# clock_driver_board.net
KiCad netlist of a schematic drawn in EAGLE
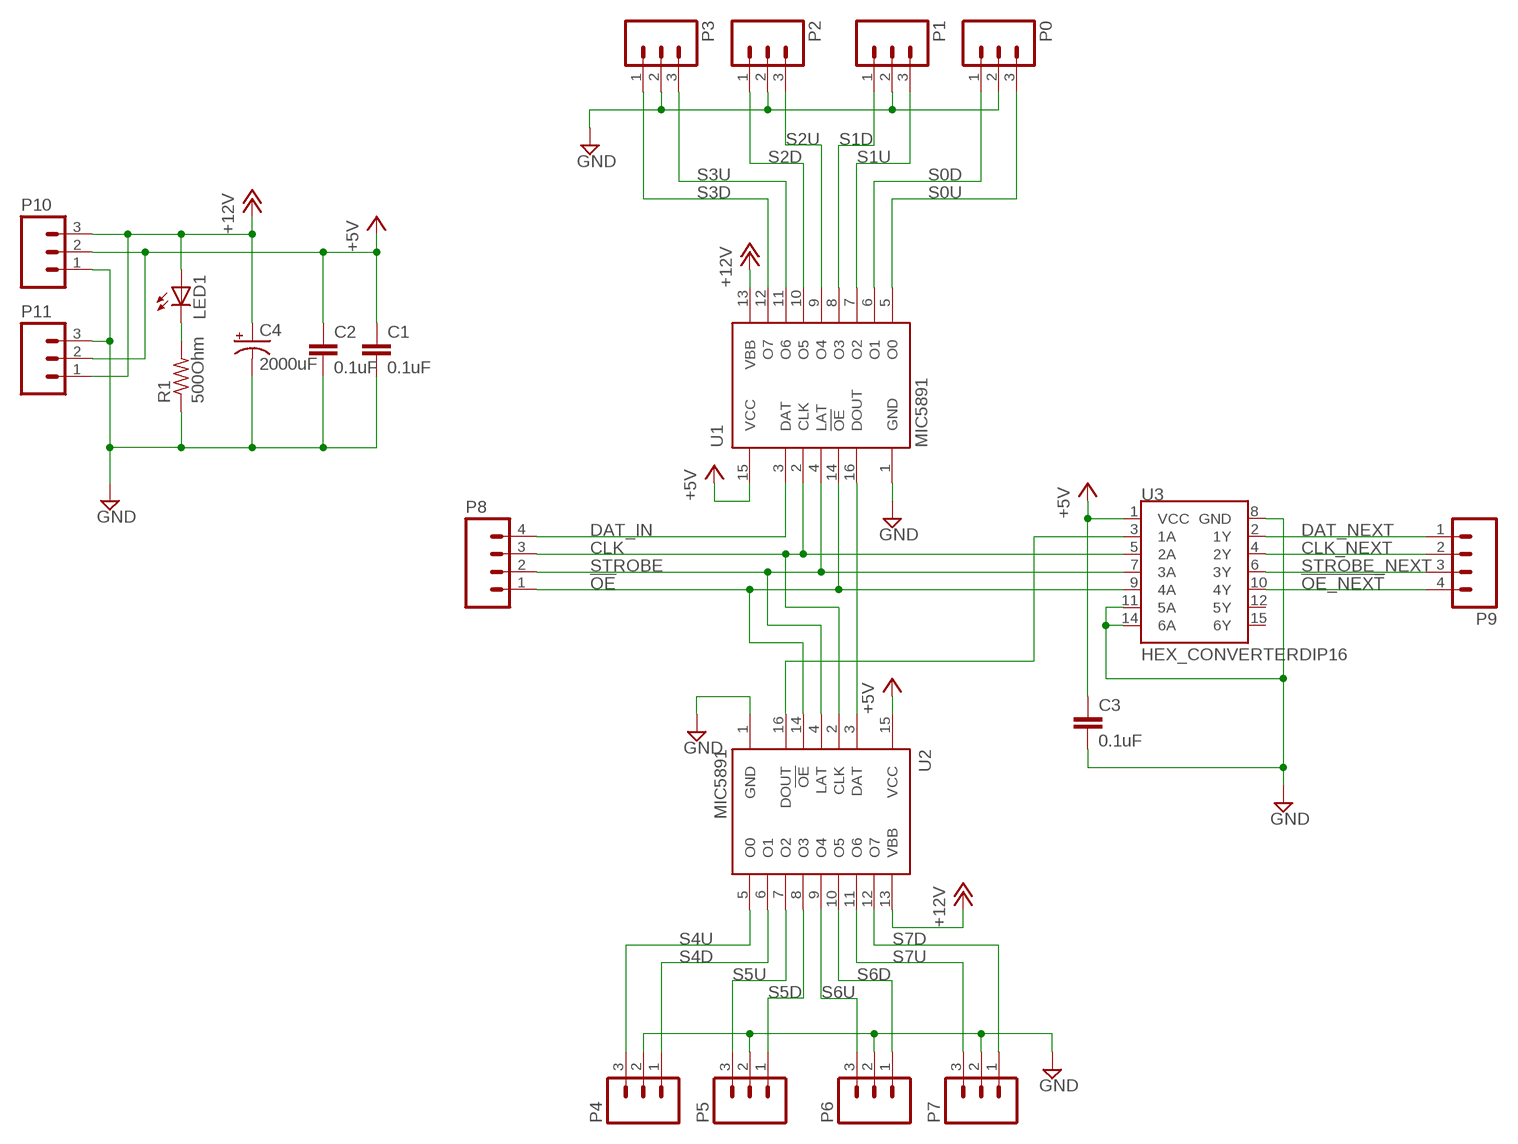
[diagram p0: schematic, sheet 1]

(export (version "E")
  (design (tool "Eeschema 10.0.6"))
  (components
    (comp (ref "C1")
      (value "0.1uF")
      (footprint "eagle-import:C2.5-2")
      (libsource (lib "eagle-import") (part "C2.5/2"))
    )
    (comp (ref "C2")
      (value "0.1uF")
      (footprint "eagle-import:C2.5-2")
      (libsource (lib "eagle-import") (part "C2.5/2"))
    )
    (comp (ref "C3")
      (value "0.1uF")
      (footprint "eagle-import:C2.5-2")
      (libsource (lib "eagle-import") (part "C2.5/2"))
    )
    (comp (ref "C4")
      (value "2000uF")
      (footprint "eagle-import:E7,5-16")
      (libsource (lib "eagle-import") (part "CPOL-USE7.5-16"))
    )
    (comp (ref "LED1")
      (value "LED3MM")
      (footprint "eagle-import:LED3MM")
      (libsource (lib "eagle-import") (part "LED3MM"))
    )
    (comp (ref "P0")
      (value "M03LONGPADS")
      (footprint "eagle-import:1X03_LONGPADS")
      (libsource (lib "eagle-import") (part "M03LONGPADS"))
    )
    (comp (ref "P1")
      (value "M03LONGPADS")
      (footprint "eagle-import:1X03_LONGPADS")
      (libsource (lib "eagle-import") (part "M03LONGPADS"))
    )
    (comp (ref "P2")
      (value "M03LONGPADS")
      (footprint "eagle-import:1X03_LONGPADS")
      (libsource (lib "eagle-import") (part "M03LONGPADS"))
    )
    (comp (ref "P3")
      (value "M03LONGPADS")
      (footprint "eagle-import:1X03_LONGPADS")
      (libsource (lib "eagle-import") (part "M03LONGPADS"))
    )
    (comp (ref "P4")
      (value "M03LONGPADS")
      (footprint "eagle-import:1X03_LONGPADS")
      (libsource (lib "eagle-import") (part "M03LONGPADS"))
    )
    (comp (ref "P5")
      (value "M03LONGPADS")
      (footprint "eagle-import:1X03_LONGPADS")
      (libsource (lib "eagle-import") (part "M03LONGPADS"))
    )
    (comp (ref "P6")
      (value "M03LONGPADS")
      (footprint "eagle-import:1X03_LONGPADS")
      (libsource (lib "eagle-import") (part "M03LONGPADS"))
    )
    (comp (ref "P7")
      (value "M03LONGPADS")
      (footprint "eagle-import:1X03_LONGPADS")
      (libsource (lib "eagle-import") (part "M03LONGPADS"))
    )
    (comp (ref "P8")
      (value "M04LONGPADS")
      (footprint "eagle-import:1X04_LONGPADS")
      (libsource (lib "eagle-import") (part "M04LONGPADS"))
    )
    (comp (ref "P9")
      (value "M04LONGPADS")
      (footprint "eagle-import:1X04_LONGPADS")
      (libsource (lib "eagle-import") (part "M04LONGPADS"))
    )
    (comp (ref "P10")
      (value "M03SCREW")
      (footprint "eagle-import:SCREWTERMINAL-3.5MM-3")
      (libsource (lib "eagle-import") (part "M03SCREW"))
    )
    (comp (ref "P11")
      (value "M03SCREW")
      (footprint "eagle-import:SCREWTERMINAL-3.5MM-3")
      (libsource (lib "eagle-import") (part "M03SCREW"))
    )
    (comp (ref "R1")
      (value "500Ohm")
      (footprint "eagle-import:0204_7")
      (libsource (lib "eagle-import") (part "R-US_0204/7"))
    )
    (comp (ref "U1")
      (value "MIC5891")
      (footprint "eagle-import:DIL16")
      (libsource (lib "eagle-import") (part "MIC5891"))
    )
    (comp (ref "U2")
      (value "MIC5891")
      (footprint "eagle-import:DIL16")
      (libsource (lib "eagle-import") (part "MIC5891"))
    )
    (comp (ref "U3")
      (value "HEX_CONVERTERDIP16")
      (footprint "eagle-import:DIL16")
      (libsource (lib "eagle-import") (part "HEX_CONVERTERDIP16"))
    )
  )
  (nets
    (net (code "1") (name "+5V") (class "Default")
      (node (ref "C1") (pin "1") (pinfunction "1_1") (pintype "passive"))
      (node (ref "C2") (pin "1") (pinfunction "1_1") (pintype "passive"))
      (node (ref "C3") (pin "1") (pinfunction "1_1") (pintype "passive"))
      (node (ref "P10") (pin "2") (pinfunction "2_2") (pintype "passive"))
      (node (ref "P11") (pin "2") (pinfunction "2_2") (pintype "passive"))
      (node (ref "U1") (pin "15") (pinfunction "VCC_15") (pintype "power_in"))
      (node (ref "U2") (pin "15") (pinfunction "VCC_15") (pintype "power_in"))
      (node (ref "U3") (pin "1") (pinfunction "VCC_1") (pintype "bidirectional"))
    )
    (net (code "2") (name "+12V") (class "Default")
      (node (ref "C4") (pin "+") (pinfunction "+_+") (pintype "passive"))
      (node (ref "LED1") (pin "A") (pinfunction "A_A") (pintype "passive"))
      (node (ref "P10") (pin "3") (pinfunction "3_3") (pintype "passive"))
      (node (ref "P11") (pin "1") (pinfunction "1_1") (pintype "passive"))
      (node (ref "U1") (pin "13") (pinfunction "VBB_13") (pintype "power_in"))
      (node (ref "U2") (pin "13") (pinfunction "VBB_13") (pintype "power_in"))
    )
    (net (code "3") (name "/CLK") (class "Default")
      (node (ref "P8") (pin "3") (pinfunction "3_3") (pintype "passive"))
      (node (ref "U1") (pin "2") (pinfunction "CLK_2") (pintype "bidirectional"))
      (node (ref "U2") (pin "2") (pinfunction "CLK_2") (pintype "bidirectional"))
      (node (ref "U3") (pin "5") (pinfunction "2A_5") (pintype "bidirectional"))
    )
    (net (code "4") (name "/CLK_NEXT") (class "Default")
      (node (ref "P9") (pin "2") (pinfunction "2_2") (pintype "passive"))
      (node (ref "U3") (pin "4") (pinfunction "2Y_4") (pintype "bidirectional"))
    )
    (net (code "5") (name "/DAT_IN") (class "Default")
      (node (ref "P8") (pin "4") (pinfunction "4_4") (pintype "passive"))
      (node (ref "U1") (pin "3") (pinfunction "DAT_3") (pintype "input"))
    )
    (net (code "6") (name "/DAT_NEXT") (class "Default")
      (node (ref "P9") (pin "1") (pinfunction "1_1") (pintype "passive"))
      (node (ref "U3") (pin "2") (pinfunction "1Y_2") (pintype "bidirectional"))
    )
    (net (code "7") (name "/S0D") (class "Default")
      (node (ref "P0") (pin "1") (pinfunction "1_1") (pintype "passive"))
      (node (ref "U1") (pin "6") (pinfunction "O1_6") (pintype "bidirectional"))
    )
    (net (code "8") (name "/S0U") (class "Default")
      (node (ref "P0") (pin "3") (pinfunction "3_3") (pintype "passive"))
      (node (ref "U1") (pin "5") (pinfunction "O0_5") (pintype "bidirectional"))
    )
    (net (code "9") (name "/S1D") (class "Default")
      (node (ref "P1") (pin "1") (pinfunction "1_1") (pintype "passive"))
      (node (ref "U1") (pin "8") (pinfunction "O3_8") (pintype "bidirectional"))
    )
    (net (code "10") (name "/S1U") (class "Default")
      (node (ref "P1") (pin "3") (pinfunction "3_3") (pintype "passive"))
      (node (ref "U1") (pin "7") (pinfunction "O2_7") (pintype "bidirectional"))
    )
    (net (code "11") (name "/S2D") (class "Default")
      (node (ref "P2") (pin "1") (pinfunction "1_1") (pintype "passive"))
      (node (ref "U1") (pin "10") (pinfunction "O5_10") (pintype "bidirectional"))
    )
    (net (code "12") (name "/S2U") (class "Default")
      (node (ref "P2") (pin "3") (pinfunction "3_3") (pintype "passive"))
      (node (ref "U1") (pin "9") (pinfunction "O4_9") (pintype "bidirectional"))
    )
    (net (code "13") (name "/S3D") (class "Default")
      (node (ref "P3") (pin "1") (pinfunction "1_1") (pintype "passive"))
      (node (ref "U1") (pin "12") (pinfunction "O7_12") (pintype "bidirectional"))
    )
    (net (code "14") (name "/S3U") (class "Default")
      (node (ref "P3") (pin "3") (pinfunction "3_3") (pintype "passive"))
      (node (ref "U1") (pin "11") (pinfunction "O6_11") (pintype "bidirectional"))
    )
    (net (code "15") (name "/S4D") (class "Default")
      (node (ref "P4") (pin "1") (pinfunction "1_1") (pintype "passive"))
      (node (ref "U2") (pin "6") (pinfunction "O1_6") (pintype "bidirectional"))
    )
    (net (code "16") (name "/S4U") (class "Default")
      (node (ref "P4") (pin "3") (pinfunction "3_3") (pintype "passive"))
      (node (ref "U2") (pin "5") (pinfunction "O0_5") (pintype "bidirectional"))
    )
    (net (code "17") (name "/S5D") (class "Default")
      (node (ref "P5") (pin "1") (pinfunction "1_1") (pintype "passive"))
      (node (ref "U2") (pin "8") (pinfunction "O3_8") (pintype "bidirectional"))
    )
    (net (code "18") (name "/S5U") (class "Default")
      (node (ref "P5") (pin "3") (pinfunction "3_3") (pintype "passive"))
      (node (ref "U2") (pin "7") (pinfunction "O2_7") (pintype "bidirectional"))
    )
    (net (code "19") (name "/S6D") (class "Default")
      (node (ref "P6") (pin "1") (pinfunction "1_1") (pintype "passive"))
      (node (ref "U2") (pin "10") (pinfunction "O5_10") (pintype "bidirectional"))
    )
    (net (code "20") (name "/S6U") (class "Default")
      (node (ref "P6") (pin "3") (pinfunction "3_3") (pintype "passive"))
      (node (ref "U2") (pin "9") (pinfunction "O4_9") (pintype "bidirectional"))
    )
    (net (code "21") (name "/S7D") (class "Default")
      (node (ref "P7") (pin "1") (pinfunction "1_1") (pintype "passive"))
      (node (ref "U2") (pin "12") (pinfunction "O7_12") (pintype "bidirectional"))
    )
    (net (code "22") (name "/S7U") (class "Default")
      (node (ref "P7") (pin "3") (pinfunction "3_3") (pintype "passive"))
      (node (ref "U2") (pin "11") (pinfunction "O6_11") (pintype "bidirectional"))
    )
    (net (code "23") (name "/STROBE") (class "Default")
      (node (ref "P8") (pin "2") (pinfunction "2_2") (pintype "passive"))
      (node (ref "U1") (pin "4") (pinfunction "LAT_4") (pintype "bidirectional"))
      (node (ref "U2") (pin "4") (pinfunction "LAT_4") (pintype "bidirectional"))
      (node (ref "U3") (pin "7") (pinfunction "3A_7") (pintype "bidirectional"))
    )
    (net (code "24") (name "/STROBE_NEXT") (class "Default")
      (node (ref "P9") (pin "3") (pinfunction "3_3") (pintype "passive"))
      (node (ref "U3") (pin "6") (pinfunction "3Y_6") (pintype "bidirectional"))
    )
    (net (code "25") (name "/~{OE_NEXT}") (class "Default")
      (node (ref "P9") (pin "4") (pinfunction "4_4") (pintype "passive"))
      (node (ref "U3") (pin "10") (pinfunction "4Y_10") (pintype "bidirectional"))
    )
    (net (code "26") (name "/~{OE}") (class "Default")
      (node (ref "P8") (pin "1") (pinfunction "1_1") (pintype "passive"))
      (node (ref "U1") (pin "14") (pinfunction "~{OE}_14") (pintype "bidirectional"))
      (node (ref "U2") (pin "14") (pinfunction "~{OE}_14") (pintype "bidirectional"))
      (node (ref "U3") (pin "9") (pinfunction "4A_9") (pintype "bidirectional"))
    )
    (net (code "27") (name "GND") (class "Default")
      (node (ref "C1") (pin "2") (pinfunction "2_2") (pintype "passive"))
      (node (ref "C2") (pin "2") (pinfunction "2_2") (pintype "passive"))
      (node (ref "C3") (pin "2") (pinfunction "2_2") (pintype "passive"))
      (node (ref "C4") (pin "-") (pinfunction "-_-") (pintype "passive"))
      (node (ref "P0") (pin "2") (pinfunction "2_2") (pintype "passive"))
      (node (ref "P1") (pin "2") (pinfunction "2_2") (pintype "passive"))
      (node (ref "P10") (pin "1") (pinfunction "1_1") (pintype "passive"))
      (node (ref "P11") (pin "3") (pinfunction "3_3") (pintype "passive"))
      (node (ref "P2") (pin "2") (pinfunction "2_2") (pintype "passive"))
      (node (ref "P3") (pin "2") (pinfunction "2_2") (pintype "passive"))
      (node (ref "P4") (pin "2") (pinfunction "2_2") (pintype "passive"))
      (node (ref "P5") (pin "2") (pinfunction "2_2") (pintype "passive"))
      (node (ref "P6") (pin "2") (pinfunction "2_2") (pintype "passive"))
      (node (ref "P7") (pin "2") (pinfunction "2_2") (pintype "passive"))
      (node (ref "R1") (pin "1") (pinfunction "1_1") (pintype "passive"))
      (node (ref "U1") (pin "1") (pinfunction "GND_1") (pintype "power_in"))
      (node (ref "U2") (pin "1") (pinfunction "GND_1") (pintype "power_in"))
      (node (ref "U3") (pin "11") (pinfunction "5A_11") (pintype "bidirectional"))
      (node (ref "U3") (pin "14") (pinfunction "6A_14") (pintype "bidirectional"))
      (node (ref "U3") (pin "8") (pinfunction "GND_8") (pintype "bidirectional"))
    )
    (net (code "28") (name "Net-(LED1-C)") (class "Default")
      (node (ref "LED1") (pin "K") (pinfunction "C_K") (pintype "passive"))
      (node (ref "R1") (pin "2") (pinfunction "2_2") (pintype "passive"))
    )
    (net (code "29") (name "Net-(U1-DOUT)") (class "Default")
      (node (ref "U1") (pin "16") (pinfunction "DOUT_16") (pintype "output"))
      (node (ref "U2") (pin "3") (pinfunction "DAT_3") (pintype "input"))
    )
    (net (code "30") (name "Net-(U2-DOUT)") (class "Default")
      (node (ref "U2") (pin "16") (pinfunction "DOUT_16") (pintype "output"))
      (node (ref "U3") (pin "3") (pinfunction "1A_3") (pintype "bidirectional"))
    )
    (net (code "31") (name "unconnected-(U3-5Y-Pad12)") (class "Default")
      (node (ref "U3") (pin "12") (pinfunction "5Y_12") (pintype "bidirectional"))
    )
    (net (code "32") (name "unconnected-(U3-6Y-Pad15)") (class "Default")
      (node (ref "U3") (pin "15") (pinfunction "6Y_15") (pintype "bidirectional"))
    )
  )
)
